# Breadboard.net
KiCad netlist of a schematic drawn in EAGLE
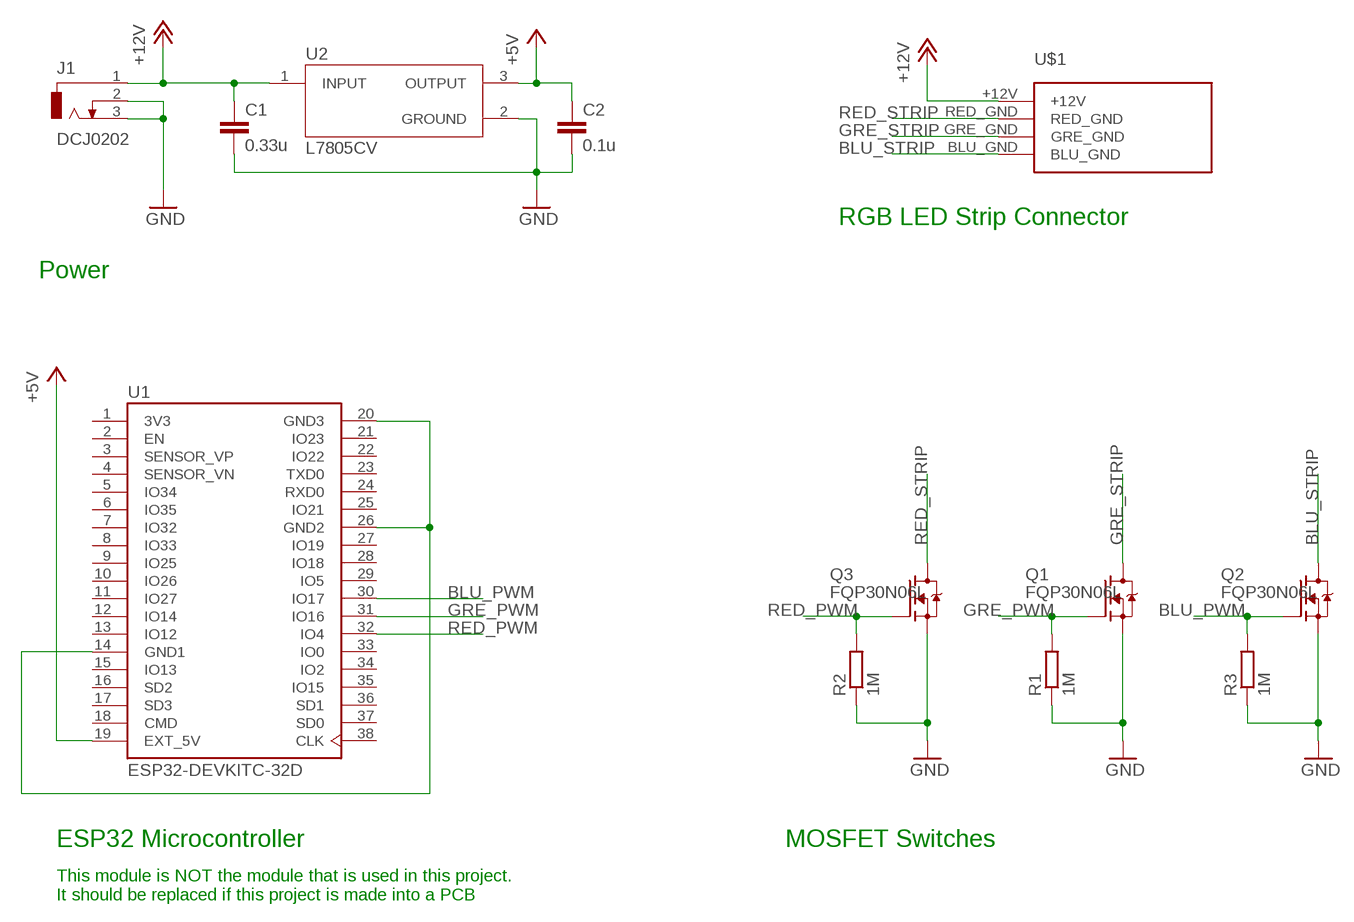
[diagram p0: schematic, sheet 1]

(export (version "E")
  (design (tool "Eeschema 10.0.6"))
  (components
    (comp (ref "C1")
      (value "0.33u")
      (footprint "eagle-import:C050-025X075")
      (libsource (lib "eagle-import") (part "C-EU050-025X075"))
    )
    (comp (ref "C2")
      (value "0.1u")
      (footprint "eagle-import:C050-025X075")
      (libsource (lib "eagle-import") (part "C-EU050-025X075"))
    )
    (comp (ref "J1")
      (value "DCJ0202")
      (footprint "eagle-import:DCJ0202")
      (libsource (lib "eagle-import") (part "DCJ0202"))
    )
    (comp (ref "Q1")
      (value "FQP30N06L")
      (footprint "eagle-import:TO220V")
      (fields (field (name "MF") "ON Semiconductor"))
      (libsource (lib "eagle-import") (part "FQP30N06L"))
    )
    (comp (ref "Q2")
      (value "FQP30N06L")
      (footprint "eagle-import:TO220V")
      (fields (field (name "MF") "ON Semiconductor"))
      (libsource (lib "eagle-import") (part "FQP30N06L"))
    )
    (comp (ref "Q3")
      (value "FQP30N06L")
      (footprint "eagle-import:TO220V")
      (fields (field (name "MF") "ON Semiconductor"))
      (libsource (lib "eagle-import") (part "FQP30N06L"))
    )
    (comp (ref "R1")
      (value "1M")
      (footprint "eagle-import:0411_12")
      (libsource (lib "eagle-import") (part "R-EU_0411/12"))
    )
    (comp (ref "R2")
      (value "1M")
      (footprint "eagle-import:0411_12")
      (libsource (lib "eagle-import") (part "R-EU_0411/12"))
    )
    (comp (ref "R3")
      (value "1M")
      (footprint "eagle-import:0411_12")
      (libsource (lib "eagle-import") (part "R-EU_0411/12"))
    )
    (comp (ref "U$1")
      (value "RGB_LED_STRIP_COM_ANNODE")
      (footprint "eagle-import:RGB_LED_STRIP_COM_ANNODE")
      (libsource (lib "eagle-import") (part "RGB_LED_STRIP_COM_ANNODE"))
    )
    (comp (ref "U1")
      (value "ESP32-DEVKITC-32D")
      (footprint "eagle-import:MODULE_ESP32-DEVKITC-32D")
      (fields (field (name "MF") "Espressif Systems"))
      (libsource (lib "eagle-import") (part "ESP32-DEVKITC-32D"))
    )
    (comp (ref "U2")
      (value "L7805CV")
      (footprint "eagle-import:TO255P1040X460X1968-3")
      (fields (field (name "MF") "STMicroelectronics"))
      (libsource (lib "eagle-import") (part "L7805CV"))
    )
  )
  (nets
    (net (code "1") (name "+5V") (class "Default")
      (node (ref "C2") (pin "1") (pinfunction "1_1") (pintype "passive"))
      (node (ref "U1") (pin "19") (pinfunction "EXT_5V_19") (pintype "power_in"))
      (node (ref "U2") (pin "3") (pinfunction "OUTPUT_3") (pintype "output"))
    )
    (net (code "2") (name "+12V") (class "Default")
      (node (ref "C1") (pin "1") (pinfunction "1_1") (pintype "passive"))
      (node (ref "J1") (pin "1") (pinfunction "1_1") (pintype "passive"))
      (node (ref "U$1") (pin "+12V") (pinfunction "+12V_+12V") (pintype "bidirectional"))
      (node (ref "U2") (pin "1") (pinfunction "INPUT_1") (pintype "input"))
    )
    (net (code "3") (name "/3V3") (class "Default")
      (node (ref "U1") (pin "1") (pinfunction "3V3_1") (pintype "power_in"))
    )
    (net (code "4") (name "/BLU_PWM") (class "Default")
      (node (ref "Q2") (pin "1") (pinfunction "G_1") (pintype "passive"))
      (node (ref "R3") (pin "2") (pinfunction "2_2") (pintype "passive"))
      (node (ref "U1") (pin "30") (pinfunction "IO17_30") (pintype "bidirectional"))
    )
    (net (code "5") (name "/BLU_STRIP") (class "Default")
      (node (ref "Q2") (pin "2") (pinfunction "D_2") (pintype "passive"))
      (node (ref "U$1") (pin "BLU_GND") (pinfunction "BLU_GND_BLU_GND") (pintype "bidirectional"))
    )
    (net (code "6") (name "/GRE_PWM") (class "Default")
      (node (ref "Q1") (pin "1") (pinfunction "G_1") (pintype "passive"))
      (node (ref "R1") (pin "2") (pinfunction "2_2") (pintype "passive"))
      (node (ref "U1") (pin "31") (pinfunction "IO16_31") (pintype "bidirectional"))
    )
    (net (code "7") (name "/GRE_STRIP") (class "Default")
      (node (ref "Q1") (pin "2") (pinfunction "D_2") (pintype "passive"))
      (node (ref "U$1") (pin "GRE_GND") (pinfunction "GRE_GND_GRE_GND") (pintype "bidirectional"))
    )
    (net (code "8") (name "/RED_PWM") (class "Default")
      (node (ref "Q3") (pin "1") (pinfunction "G_1") (pintype "passive"))
      (node (ref "R2") (pin "2") (pinfunction "2_2") (pintype "passive"))
      (node (ref "U1") (pin "32") (pinfunction "IO4_32") (pintype "bidirectional"))
    )
    (net (code "9") (name "/RED_STRIP") (class "Default")
      (node (ref "Q3") (pin "2") (pinfunction "D_2") (pintype "passive"))
      (node (ref "U$1") (pin "RED_GND") (pinfunction "RED_GND_RED_GND") (pintype "bidirectional"))
    )
    (net (code "10") (name "GND") (class "Default")
      (node (ref "C1") (pin "2") (pinfunction "2_2") (pintype "passive"))
      (node (ref "C2") (pin "2") (pinfunction "2_2") (pintype "passive"))
      (node (ref "J1") (pin "2") (pinfunction "2_2") (pintype "passive"))
      (node (ref "J1") (pin "3") (pinfunction "3_3") (pintype "passive"))
      (node (ref "Q1") (pin "3") (pinfunction "S_3") (pintype "passive"))
      (node (ref "Q2") (pin "3") (pinfunction "S_3") (pintype "passive"))
      (node (ref "Q3") (pin "3") (pinfunction "S_3") (pintype "passive"))
      (node (ref "R1") (pin "1") (pinfunction "1_1") (pintype "passive"))
      (node (ref "R2") (pin "1") (pinfunction "1_1") (pintype "passive"))
      (node (ref "R3") (pin "1") (pinfunction "1_1") (pintype "passive"))
      (node (ref "U2") (pin "2") (pinfunction "GROUND_2") (pintype "power_in"))
    )
    (net (code "11") (name "Net-(U1-GND1)") (class "Default")
      (node (ref "U1") (pin "14") (pinfunction "GND1_14") (pintype "power_in"))
      (node (ref "U1") (pin "20") (pinfunction "GND3_20") (pintype "power_in"))
      (node (ref "U1") (pin "26") (pinfunction "GND2_26") (pintype "power_in"))
    )
    (net (code "12") (name "unconnected-(U1-CLK-Pad38)") (class "Default")
      (node (ref "U1") (pin "38") (pinfunction "CLK_38") (pintype "input"))
    )
    (net (code "13") (name "unconnected-(U1-CMD-Pad18)") (class "Default")
      (node (ref "U1") (pin "18") (pinfunction "CMD_18") (pintype "bidirectional"))
    )
    (net (code "14") (name "unconnected-(U1-EN-Pad2)") (class "Default")
      (node (ref "U1") (pin "2") (pinfunction "EN_2") (pintype "input"))
    )
    (net (code "15") (name "unconnected-(U1-IO0-Pad33)") (class "Default")
      (node (ref "U1") (pin "33") (pinfunction "IO0_33") (pintype "bidirectional"))
    )
    (net (code "16") (name "unconnected-(U1-IO2-Pad34)") (class "Default")
      (node (ref "U1") (pin "34") (pinfunction "IO2_34") (pintype "bidirectional"))
    )
    (net (code "17") (name "unconnected-(U1-IO5-Pad29)") (class "Default")
      (node (ref "U1") (pin "29") (pinfunction "IO5_29") (pintype "bidirectional"))
    )
    (net (code "18") (name "unconnected-(U1-IO12-Pad13)") (class "Default")
      (node (ref "U1") (pin "13") (pinfunction "IO12_13") (pintype "bidirectional"))
    )
    (net (code "19") (name "unconnected-(U1-IO13-Pad15)") (class "Default")
      (node (ref "U1") (pin "15") (pinfunction "IO13_15") (pintype "bidirectional"))
    )
    (net (code "20") (name "unconnected-(U1-IO14-Pad12)") (class "Default")
      (node (ref "U1") (pin "12") (pinfunction "IO14_12") (pintype "bidirectional"))
    )
    (net (code "21") (name "unconnected-(U1-IO15-Pad35)") (class "Default")
      (node (ref "U1") (pin "35") (pinfunction "IO15_35") (pintype "bidirectional"))
    )
    (net (code "22") (name "unconnected-(U1-IO18-Pad28)") (class "Default")
      (node (ref "U1") (pin "28") (pinfunction "IO18_28") (pintype "bidirectional"))
    )
    (net (code "23") (name "unconnected-(U1-IO19-Pad27)") (class "Default")
      (node (ref "U1") (pin "27") (pinfunction "IO19_27") (pintype "bidirectional"))
    )
    (net (code "24") (name "unconnected-(U1-IO21-Pad25)") (class "Default")
      (node (ref "U1") (pin "25") (pinfunction "IO21_25") (pintype "bidirectional"))
    )
    (net (code "25") (name "unconnected-(U1-IO22-Pad22)") (class "Default")
      (node (ref "U1") (pin "22") (pinfunction "IO22_22") (pintype "bidirectional"))
    )
    (net (code "26") (name "unconnected-(U1-IO23-Pad21)") (class "Default")
      (node (ref "U1") (pin "21") (pinfunction "IO23_21") (pintype "bidirectional"))
    )
    (net (code "27") (name "unconnected-(U1-IO25-Pad9)") (class "Default")
      (node (ref "U1") (pin "9") (pinfunction "IO25_9") (pintype "bidirectional"))
    )
    (net (code "28") (name "unconnected-(U1-IO26-Pad10)") (class "Default")
      (node (ref "U1") (pin "10") (pinfunction "IO26_10") (pintype "bidirectional"))
    )
    (net (code "29") (name "unconnected-(U1-IO27-Pad11)") (class "Default")
      (node (ref "U1") (pin "11") (pinfunction "IO27_11") (pintype "bidirectional"))
    )
    (net (code "30") (name "unconnected-(U1-IO32-Pad7)") (class "Default")
      (node (ref "U1") (pin "7") (pinfunction "IO32_7") (pintype "bidirectional"))
    )
    (net (code "31") (name "unconnected-(U1-IO33-Pad8)") (class "Default")
      (node (ref "U1") (pin "8") (pinfunction "IO33_8") (pintype "bidirectional"))
    )
    (net (code "32") (name "unconnected-(U1-IO34-Pad5)") (class "Default")
      (node (ref "U1") (pin "5") (pinfunction "IO34_5") (pintype "bidirectional"))
    )
    (net (code "33") (name "unconnected-(U1-IO35-Pad6)") (class "Default")
      (node (ref "U1") (pin "6") (pinfunction "IO35_6") (pintype "bidirectional"))
    )
    (net (code "34") (name "unconnected-(U1-RXD0-Pad24)") (class "Default")
      (node (ref "U1") (pin "24") (pinfunction "RXD0_24") (pintype "input"))
    )
    (net (code "35") (name "unconnected-(U1-SD0-Pad37)") (class "Default")
      (node (ref "U1") (pin "37") (pinfunction "SD0_37") (pintype "bidirectional"))
    )
    (net (code "36") (name "unconnected-(U1-SD1-Pad36)") (class "Default")
      (node (ref "U1") (pin "36") (pinfunction "SD1_36") (pintype "bidirectional"))
    )
    (net (code "37") (name "unconnected-(U1-SD2-Pad16)") (class "Default")
      (node (ref "U1") (pin "16") (pinfunction "SD2_16") (pintype "bidirectional"))
    )
    (net (code "38") (name "unconnected-(U1-SD3-Pad17)") (class "Default")
      (node (ref "U1") (pin "17") (pinfunction "SD3_17") (pintype "bidirectional"))
    )
    (net (code "39") (name "unconnected-(U1-SENSOR_VN-Pad4)") (class "Default")
      (node (ref "U1") (pin "4") (pinfunction "SENSOR_VN_4") (pintype "input"))
    )
    (net (code "40") (name "unconnected-(U1-SENSOR_VP-Pad3)") (class "Default")
      (node (ref "U1") (pin "3") (pinfunction "SENSOR_VP_3") (pintype "input"))
    )
    (net (code "41") (name "unconnected-(U1-TXD0-Pad23)") (class "Default")
      (node (ref "U1") (pin "23") (pinfunction "TXD0_23") (pintype "output"))
    )
  )
)
